# 230v.net
KiCad netlist of a schematic drawn in EAGLE
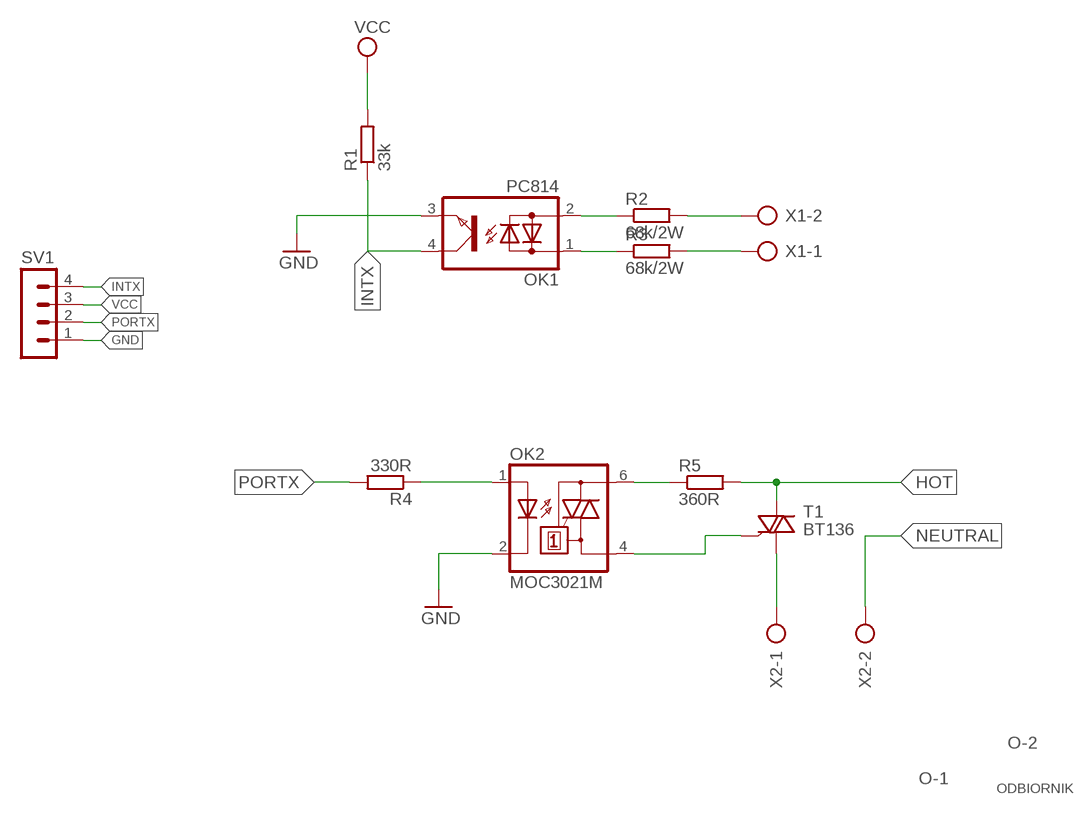
[diagram p0: schematic, sheet 1]

(export (version "E")
  (design (tool "Eeschema 10.0.6"))
  (components
    (comp (ref "OK1")
      (value "PC814")
      (footprint "eagle-import:DIL04")
      (libsource (lib "eagle-import") (part "PC814"))
    )
    (comp (ref "OK2")
      (value "MOC3021M")
      (footprint "eagle-import:DIL06")
      (fields (field (name "MF") "FAIRCHILD SEMICONDUCTOR") (field (name "MPN") "MOC3021-M"))
      (libsource (lib "eagle-import") (part "MOC30M21"))
    )
    (comp (ref "R1")
      (value "33k")
      (footprint "eagle-import:R0805")
      (libsource (lib "eagle-import") (part "R-EU_R0805"))
    )
    (comp (ref "R2")
      (value "68k/2W")
      (footprint "eagle-import:0309_12")
      (libsource (lib "eagle-import") (part "R-EU_0309/12"))
    )
    (comp (ref "R3")
      (value "68k/2W")
      (footprint "eagle-import:0309_12")
      (libsource (lib "eagle-import") (part "R-EU_0309/12"))
    )
    (comp (ref "R4")
      (value "330R")
      (footprint "eagle-import:R0805")
      (libsource (lib "eagle-import") (part "R-EU_R0805"))
    )
    (comp (ref "R5")
      (value "360R")
      (footprint "eagle-import:0207_7")
      (libsource (lib "eagle-import") (part "R-EU_0207/7"))
    )
    (comp (ref "SV1")
      (value "MA04-1")
      (footprint "eagle-import:MA04-1")
      (libsource (lib "eagle-import") (part "MA04-1"))
    )
    (comp (ref "T1")
      (value "BT136")
      (footprint "eagle-import:TO220AB")
      (libsource (lib "eagle-import") (part "BT136"))
    )
    (comp (ref "X1")
      (value "AK300/2")
      (footprint "eagle-import:AK300_2")
      (libsource (lib "eagle-import") (part "AK300/2"))
    )
    (comp (ref "X2")
      (value "AK300/2")
      (footprint "eagle-import:AK300_2")
      (libsource (lib "eagle-import") (part "AK300/2"))
    )
  )
  (nets
    (net (code "1") (name "GND") (class "Default")
      (node (ref "OK1") (pin "3") (pinfunction "E_3") (pintype "passive"))
      (node (ref "OK2") (pin "2") (pinfunction "C_2") (pintype "passive"))
      (node (ref "SV1") (pin "1") (pinfunction "1_1") (pintype "passive"))
    )
    (net (code "2") (name "HOT") (class "Default")
      (node (ref "R2") (pin "2") (pinfunction "2_2") (pintype "passive"))
      (node (ref "R5") (pin "2") (pinfunction "2_2") (pintype "passive"))
      (node (ref "T1") (pin "2") (pinfunction "A2_2") (pintype "passive"))
      (node (ref "X1") (pin "2") (pinfunction "KL_2") (pintype "passive"))
    )
    (net (code "3") (name "INTX") (class "Default")
      (node (ref "OK1") (pin "4") (pinfunction "C_4") (pintype "passive"))
      (node (ref "R1") (pin "1") (pinfunction "1_1") (pintype "passive"))
      (node (ref "SV1") (pin "4") (pinfunction "4_4") (pintype "passive"))
    )
    (net (code "4") (name "NEUTRAL") (class "Default")
      (node (ref "R3") (pin "2") (pinfunction "2_2") (pintype "passive"))
      (node (ref "X1") (pin "1") (pinfunction "KL_1") (pintype "passive"))
      (node (ref "X2") (pin "2") (pinfunction "KL_2") (pintype "passive"))
    )
    (net (code "5") (name "Net-(OK1-AC1)") (class "Default")
      (node (ref "OK1") (pin "1") (pinfunction "AC1_1") (pintype "passive"))
      (node (ref "R3") (pin "1") (pinfunction "1_1") (pintype "passive"))
    )
    (net (code "6") (name "Net-(OK1-AC2)") (class "Default")
      (node (ref "OK1") (pin "2") (pinfunction "AC2_2") (pintype "passive"))
      (node (ref "R2") (pin "1") (pinfunction "1_1") (pintype "passive"))
    )
    (net (code "7") (name "Net-(OK2-A)") (class "Default")
      (node (ref "OK2") (pin "1") (pinfunction "A_1") (pintype "passive"))
      (node (ref "R4") (pin "1") (pinfunction "1_1") (pintype "passive"))
    )
    (net (code "8") (name "Net-(OK2-A1)") (class "Default")
      (node (ref "OK2") (pin "4") (pinfunction "A1_4") (pintype "passive"))
      (node (ref "T1") (pin "3") (pinfunction "G_3") (pintype "passive"))
    )
    (net (code "9") (name "Net-(OK2-A2)") (class "Default")
      (node (ref "OK2") (pin "6") (pinfunction "A2_6") (pintype "passive"))
      (node (ref "R5") (pin "1") (pinfunction "1_1") (pintype "passive"))
    )
    (net (code "10") (name "Net-(T1-A1)") (class "Default")
      (node (ref "T1") (pin "1") (pinfunction "A1_1") (pintype "passive"))
      (node (ref "X2") (pin "1") (pinfunction "KL_1") (pintype "passive"))
    )
    (net (code "11") (name "PORTX") (class "Default")
      (node (ref "R4") (pin "2") (pinfunction "2_2") (pintype "passive"))
      (node (ref "SV1") (pin "2") (pinfunction "2_2") (pintype "passive"))
    )
    (net (code "12") (name "VCC") (class "Default")
      (node (ref "R1") (pin "2") (pinfunction "2_2") (pintype "passive"))
      (node (ref "SV1") (pin "3") (pinfunction "3_3") (pintype "passive"))
    )
  )
)
